# PSO36_BREKAOUT.net
KiCad netlist of a schematic drawn in EAGLE
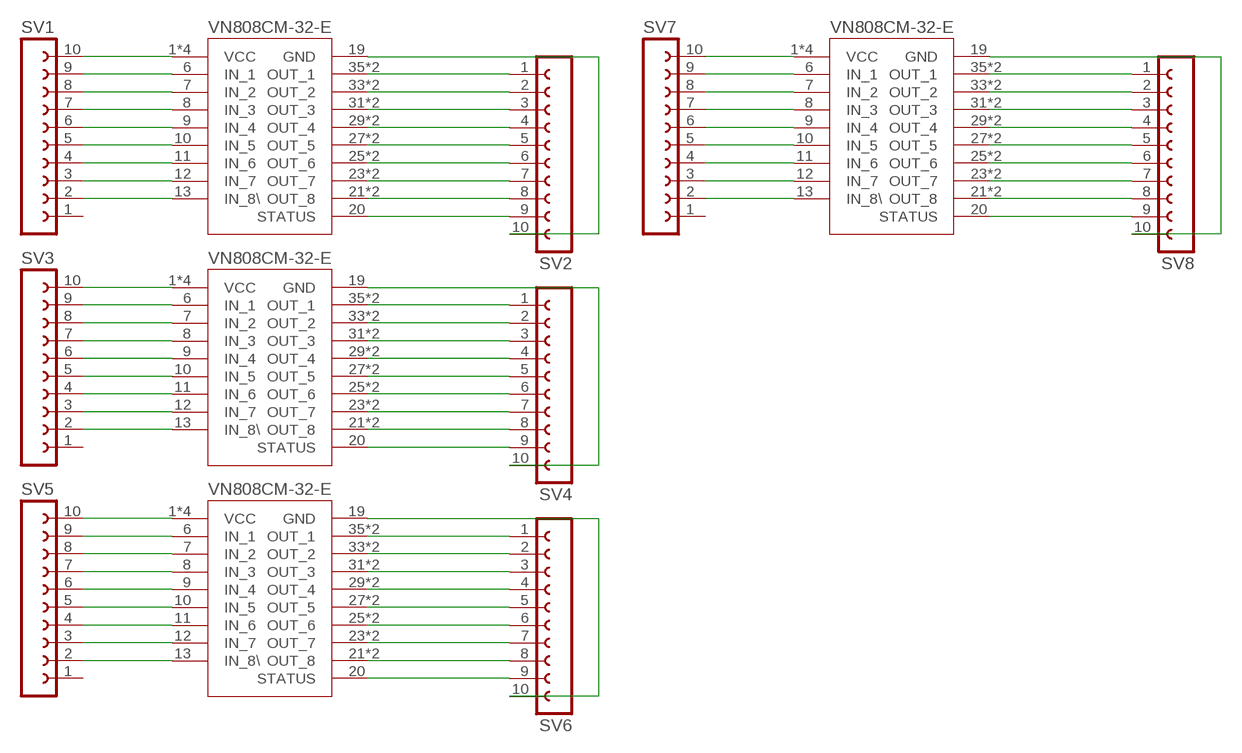
[diagram p0: schematic, sheet 1]

(export (version "E")
  (design (tool "Eeschema 10.0.6"))
  (components
    (comp (ref "SV1")
      (value "FE10-1")
      (footprint "eagle-import:FE10")
      (libsource (lib "eagle-import") (part "FE10-1"))
    )
    (comp (ref "SV2")
      (value "FE10-1")
      (footprint "eagle-import:FE10")
      (libsource (lib "eagle-import") (part "FE10-1"))
    )
    (comp (ref "SV3")
      (value "FE10-1")
      (footprint "eagle-import:FE10")
      (libsource (lib "eagle-import") (part "FE10-1"))
    )
    (comp (ref "SV4")
      (value "FE10-1")
      (footprint "eagle-import:FE10")
      (libsource (lib "eagle-import") (part "FE10-1"))
    )
    (comp (ref "SV5")
      (value "FE10-1")
      (footprint "eagle-import:FE10")
      (libsource (lib "eagle-import") (part "FE10-1"))
    )
    (comp (ref "SV6")
      (value "FE10-1")
      (footprint "eagle-import:FE10")
      (libsource (lib "eagle-import") (part "FE10-1"))
    )
    (comp (ref "SV7")
      (value "FE10-1")
      (footprint "eagle-import:FE10")
      (libsource (lib "eagle-import") (part "FE10-1"))
    )
    (comp (ref "SV8")
      (value "FE10-1")
      (footprint "eagle-import:FE10")
      (libsource (lib "eagle-import") (part "FE10-1"))
    )
    (comp (ref "U$1")
      (value "VN808CM-32-E")
      (footprint "eagle-import:PSO36")
      (libsource (lib "eagle-import") (part "VN808CM-32-E"))
    )
    (comp (ref "U$2")
      (value "VN808CM-32-E")
      (footprint "eagle-import:PSO36")
      (libsource (lib "eagle-import") (part "VN808CM-32-E"))
    )
    (comp (ref "U$3")
      (value "VN808CM-32-E")
      (footprint "eagle-import:PSO36")
      (libsource (lib "eagle-import") (part "VN808CM-32-E"))
    )
    (comp (ref "U$4")
      (value "VN808CM-32-E")
      (footprint "eagle-import:PSO36")
      (libsource (lib "eagle-import") (part "VN808CM-32-E"))
    )
  )
  (nets
    (net (code "1") (name "Net-(SV1-Pad10)") (class "Default")
      (node (ref "SV1") (pin "10") (pinfunction "10_10") (pintype "passive"))
      (node (ref "U$1") (pin "1") (pinfunction "VCC_1") (pintype "bidirectional"))
      (node (ref "U$1") (pin "M@1") (pinfunction "VCC_M@1") (pintype "bidirectional"))
      (node (ref "U$1") (pin "M@2") (pinfunction "VCC_M@2") (pintype "bidirectional"))
      (node (ref "U$1") (pin "M@3") (pinfunction "VCC_M@3") (pintype "bidirectional"))
    )
    (net (code "2") (name "Net-(SV2-Pad1)") (class "Default")
      (node (ref "SV2") (pin "1") (pinfunction "1_1") (pintype "passive"))
      (node (ref "U$1") (pin "35") (pinfunction "OUT_1_35") (pintype "bidirectional"))
      (node (ref "U$1") (pin "36") (pinfunction "OUT_1_36") (pintype "bidirectional"))
    )
    (net (code "3") (name "Net-(SV2-Pad2)") (class "Default")
      (node (ref "SV2") (pin "2") (pinfunction "2_2") (pintype "passive"))
      (node (ref "U$1") (pin "33") (pinfunction "OUT_2_33") (pintype "bidirectional"))
      (node (ref "U$1") (pin "34") (pinfunction "OUT_2_34") (pintype "bidirectional"))
    )
    (net (code "4") (name "Net-(SV2-Pad3)") (class "Default")
      (node (ref "SV2") (pin "3") (pinfunction "3_3") (pintype "passive"))
      (node (ref "U$1") (pin "31") (pinfunction "OUT_3_31") (pintype "bidirectional"))
      (node (ref "U$1") (pin "32") (pinfunction "OUT_3_32") (pintype "bidirectional"))
    )
    (net (code "5") (name "Net-(SV2-Pad4)") (class "Default")
      (node (ref "SV2") (pin "4") (pinfunction "4_4") (pintype "passive"))
      (node (ref "U$1") (pin "29") (pinfunction "OUT_4_29") (pintype "bidirectional"))
      (node (ref "U$1") (pin "30") (pinfunction "OUT_4_30") (pintype "bidirectional"))
    )
    (net (code "6") (name "Net-(SV2-Pad5)") (class "Default")
      (node (ref "SV2") (pin "5") (pinfunction "5_5") (pintype "passive"))
      (node (ref "U$1") (pin "27") (pinfunction "OUT_5_27") (pintype "bidirectional"))
      (node (ref "U$1") (pin "28") (pinfunction "OUT_5_28") (pintype "bidirectional"))
    )
    (net (code "7") (name "Net-(SV2-Pad6)") (class "Default")
      (node (ref "SV2") (pin "6") (pinfunction "6_6") (pintype "passive"))
      (node (ref "U$1") (pin "25") (pinfunction "OUT_6_25") (pintype "bidirectional"))
      (node (ref "U$1") (pin "26") (pinfunction "OUT_6_26") (pintype "bidirectional"))
    )
    (net (code "8") (name "Net-(SV2-Pad7)") (class "Default")
      (node (ref "SV2") (pin "7") (pinfunction "7_7") (pintype "passive"))
      (node (ref "U$1") (pin "23") (pinfunction "OUT_7_23") (pintype "bidirectional"))
      (node (ref "U$1") (pin "24") (pinfunction "OUT_7_24") (pintype "bidirectional"))
    )
    (net (code "9") (name "Net-(SV2-Pad8)") (class "Default")
      (node (ref "SV2") (pin "8") (pinfunction "8_8") (pintype "passive"))
      (node (ref "U$1") (pin "21") (pinfunction "OUT_8_21") (pintype "bidirectional"))
      (node (ref "U$1") (pin "22") (pinfunction "OUT_8_22") (pintype "bidirectional"))
    )
    (net (code "10") (name "Net-(SV3-Pad10)") (class "Default")
      (node (ref "SV3") (pin "10") (pinfunction "10_10") (pintype "passive"))
      (node (ref "U$2") (pin "1") (pinfunction "VCC_1") (pintype "bidirectional"))
      (node (ref "U$2") (pin "M@1") (pinfunction "VCC_M@1") (pintype "bidirectional"))
      (node (ref "U$2") (pin "M@2") (pinfunction "VCC_M@2") (pintype "bidirectional"))
      (node (ref "U$2") (pin "M@3") (pinfunction "VCC_M@3") (pintype "bidirectional"))
    )
    (net (code "11") (name "Net-(SV4-Pad1)") (class "Default")
      (node (ref "SV4") (pin "1") (pinfunction "1_1") (pintype "passive"))
      (node (ref "U$2") (pin "35") (pinfunction "OUT_1_35") (pintype "bidirectional"))
      (node (ref "U$2") (pin "36") (pinfunction "OUT_1_36") (pintype "bidirectional"))
    )
    (net (code "12") (name "Net-(SV4-Pad2)") (class "Default")
      (node (ref "SV4") (pin "2") (pinfunction "2_2") (pintype "passive"))
      (node (ref "U$2") (pin "33") (pinfunction "OUT_2_33") (pintype "bidirectional"))
      (node (ref "U$2") (pin "34") (pinfunction "OUT_2_34") (pintype "bidirectional"))
    )
    (net (code "13") (name "Net-(SV4-Pad3)") (class "Default")
      (node (ref "SV4") (pin "3") (pinfunction "3_3") (pintype "passive"))
      (node (ref "U$2") (pin "31") (pinfunction "OUT_3_31") (pintype "bidirectional"))
      (node (ref "U$2") (pin "32") (pinfunction "OUT_3_32") (pintype "bidirectional"))
    )
    (net (code "14") (name "Net-(SV4-Pad4)") (class "Default")
      (node (ref "SV4") (pin "4") (pinfunction "4_4") (pintype "passive"))
      (node (ref "U$2") (pin "29") (pinfunction "OUT_4_29") (pintype "bidirectional"))
      (node (ref "U$2") (pin "30") (pinfunction "OUT_4_30") (pintype "bidirectional"))
    )
    (net (code "15") (name "Net-(SV4-Pad5)") (class "Default")
      (node (ref "SV4") (pin "5") (pinfunction "5_5") (pintype "passive"))
      (node (ref "U$2") (pin "27") (pinfunction "OUT_5_27") (pintype "bidirectional"))
      (node (ref "U$2") (pin "28") (pinfunction "OUT_5_28") (pintype "bidirectional"))
    )
    (net (code "16") (name "Net-(SV4-Pad6)") (class "Default")
      (node (ref "SV4") (pin "6") (pinfunction "6_6") (pintype "passive"))
      (node (ref "U$2") (pin "25") (pinfunction "OUT_6_25") (pintype "bidirectional"))
      (node (ref "U$2") (pin "26") (pinfunction "OUT_6_26") (pintype "bidirectional"))
    )
    (net (code "17") (name "Net-(SV4-Pad7)") (class "Default")
      (node (ref "SV4") (pin "7") (pinfunction "7_7") (pintype "passive"))
      (node (ref "U$2") (pin "23") (pinfunction "OUT_7_23") (pintype "bidirectional"))
      (node (ref "U$2") (pin "24") (pinfunction "OUT_7_24") (pintype "bidirectional"))
    )
    (net (code "18") (name "Net-(SV4-Pad8)") (class "Default")
      (node (ref "SV4") (pin "8") (pinfunction "8_8") (pintype "passive"))
      (node (ref "U$2") (pin "21") (pinfunction "OUT_8_21") (pintype "bidirectional"))
      (node (ref "U$2") (pin "22") (pinfunction "OUT_8_22") (pintype "bidirectional"))
    )
    (net (code "19") (name "Net-(SV5-Pad10)") (class "Default")
      (node (ref "SV5") (pin "10") (pinfunction "10_10") (pintype "passive"))
      (node (ref "U$3") (pin "1") (pinfunction "VCC_1") (pintype "bidirectional"))
      (node (ref "U$3") (pin "M@1") (pinfunction "VCC_M@1") (pintype "bidirectional"))
      (node (ref "U$3") (pin "M@2") (pinfunction "VCC_M@2") (pintype "bidirectional"))
      (node (ref "U$3") (pin "M@3") (pinfunction "VCC_M@3") (pintype "bidirectional"))
    )
    (net (code "20") (name "Net-(SV6-Pad1)") (class "Default")
      (node (ref "SV6") (pin "1") (pinfunction "1_1") (pintype "passive"))
      (node (ref "U$3") (pin "35") (pinfunction "OUT_1_35") (pintype "bidirectional"))
      (node (ref "U$3") (pin "36") (pinfunction "OUT_1_36") (pintype "bidirectional"))
    )
    (net (code "21") (name "Net-(SV6-Pad2)") (class "Default")
      (node (ref "SV6") (pin "2") (pinfunction "2_2") (pintype "passive"))
      (node (ref "U$3") (pin "33") (pinfunction "OUT_2_33") (pintype "bidirectional"))
      (node (ref "U$3") (pin "34") (pinfunction "OUT_2_34") (pintype "bidirectional"))
    )
    (net (code "22") (name "Net-(SV6-Pad3)") (class "Default")
      (node (ref "SV6") (pin "3") (pinfunction "3_3") (pintype "passive"))
      (node (ref "U$3") (pin "31") (pinfunction "OUT_3_31") (pintype "bidirectional"))
      (node (ref "U$3") (pin "32") (pinfunction "OUT_3_32") (pintype "bidirectional"))
    )
    (net (code "23") (name "Net-(SV6-Pad4)") (class "Default")
      (node (ref "SV6") (pin "4") (pinfunction "4_4") (pintype "passive"))
      (node (ref "U$3") (pin "29") (pinfunction "OUT_4_29") (pintype "bidirectional"))
      (node (ref "U$3") (pin "30") (pinfunction "OUT_4_30") (pintype "bidirectional"))
    )
    (net (code "24") (name "Net-(SV6-Pad5)") (class "Default")
      (node (ref "SV6") (pin "5") (pinfunction "5_5") (pintype "passive"))
      (node (ref "U$3") (pin "27") (pinfunction "OUT_5_27") (pintype "bidirectional"))
      (node (ref "U$3") (pin "28") (pinfunction "OUT_5_28") (pintype "bidirectional"))
    )
    (net (code "25") (name "Net-(SV6-Pad6)") (class "Default")
      (node (ref "SV6") (pin "6") (pinfunction "6_6") (pintype "passive"))
      (node (ref "U$3") (pin "25") (pinfunction "OUT_6_25") (pintype "bidirectional"))
      (node (ref "U$3") (pin "26") (pinfunction "OUT_6_26") (pintype "bidirectional"))
    )
    (net (code "26") (name "Net-(SV6-Pad7)") (class "Default")
      (node (ref "SV6") (pin "7") (pinfunction "7_7") (pintype "passive"))
      (node (ref "U$3") (pin "23") (pinfunction "OUT_7_23") (pintype "bidirectional"))
      (node (ref "U$3") (pin "24") (pinfunction "OUT_7_24") (pintype "bidirectional"))
    )
    (net (code "27") (name "Net-(SV6-Pad8)") (class "Default")
      (node (ref "SV6") (pin "8") (pinfunction "8_8") (pintype "passive"))
      (node (ref "U$3") (pin "21") (pinfunction "OUT_8_21") (pintype "bidirectional"))
      (node (ref "U$3") (pin "22") (pinfunction "OUT_8_22") (pintype "bidirectional"))
    )
    (net (code "28") (name "Net-(SV7-Pad10)") (class "Default")
      (node (ref "SV7") (pin "10") (pinfunction "10_10") (pintype "passive"))
      (node (ref "U$4") (pin "1") (pinfunction "VCC_1") (pintype "bidirectional"))
      (node (ref "U$4") (pin "M@1") (pinfunction "VCC_M@1") (pintype "bidirectional"))
      (node (ref "U$4") (pin "M@2") (pinfunction "VCC_M@2") (pintype "bidirectional"))
      (node (ref "U$4") (pin "M@3") (pinfunction "VCC_M@3") (pintype "bidirectional"))
    )
    (net (code "29") (name "Net-(SV8-Pad1)") (class "Default")
      (node (ref "SV8") (pin "1") (pinfunction "1_1") (pintype "passive"))
      (node (ref "U$4") (pin "35") (pinfunction "OUT_1_35") (pintype "bidirectional"))
      (node (ref "U$4") (pin "36") (pinfunction "OUT_1_36") (pintype "bidirectional"))
    )
    (net (code "30") (name "Net-(SV8-Pad2)") (class "Default")
      (node (ref "SV8") (pin "2") (pinfunction "2_2") (pintype "passive"))
      (node (ref "U$4") (pin "33") (pinfunction "OUT_2_33") (pintype "bidirectional"))
      (node (ref "U$4") (pin "34") (pinfunction "OUT_2_34") (pintype "bidirectional"))
    )
    (net (code "31") (name "Net-(SV8-Pad3)") (class "Default")
      (node (ref "SV8") (pin "3") (pinfunction "3_3") (pintype "passive"))
      (node (ref "U$4") (pin "31") (pinfunction "OUT_3_31") (pintype "bidirectional"))
      (node (ref "U$4") (pin "32") (pinfunction "OUT_3_32") (pintype "bidirectional"))
    )
    (net (code "32") (name "Net-(SV8-Pad4)") (class "Default")
      (node (ref "SV8") (pin "4") (pinfunction "4_4") (pintype "passive"))
      (node (ref "U$4") (pin "29") (pinfunction "OUT_4_29") (pintype "bidirectional"))
      (node (ref "U$4") (pin "30") (pinfunction "OUT_4_30") (pintype "bidirectional"))
    )
    (net (code "33") (name "Net-(SV8-Pad5)") (class "Default")
      (node (ref "SV8") (pin "5") (pinfunction "5_5") (pintype "passive"))
      (node (ref "U$4") (pin "27") (pinfunction "OUT_5_27") (pintype "bidirectional"))
      (node (ref "U$4") (pin "28") (pinfunction "OUT_5_28") (pintype "bidirectional"))
    )
    (net (code "34") (name "Net-(SV8-Pad6)") (class "Default")
      (node (ref "SV8") (pin "6") (pinfunction "6_6") (pintype "passive"))
      (node (ref "U$4") (pin "25") (pinfunction "OUT_6_25") (pintype "bidirectional"))
      (node (ref "U$4") (pin "26") (pinfunction "OUT_6_26") (pintype "bidirectional"))
    )
    (net (code "35") (name "Net-(SV8-Pad7)") (class "Default")
      (node (ref "SV8") (pin "7") (pinfunction "7_7") (pintype "passive"))
      (node (ref "U$4") (pin "23") (pinfunction "OUT_7_23") (pintype "bidirectional"))
      (node (ref "U$4") (pin "24") (pinfunction "OUT_7_24") (pintype "bidirectional"))
    )
    (net (code "36") (name "Net-(SV8-Pad8)") (class "Default")
      (node (ref "SV8") (pin "8") (pinfunction "8_8") (pintype "passive"))
      (node (ref "U$4") (pin "21") (pinfunction "OUT_8_21") (pintype "bidirectional"))
      (node (ref "U$4") (pin "22") (pinfunction "OUT_8_22") (pintype "bidirectional"))
    )
    (net (code "37") (name "Net-(U$1-GND)") (class "Default")
      (node (ref "SV2") (pin "10") (pinfunction "10_10") (pintype "passive"))
      (node (ref "U$1") (pin "19") (pinfunction "GND_19") (pintype "bidirectional"))
    )
    (net (code "38") (name "Net-(U$1-IN_1)") (class "Default")
      (node (ref "SV1") (pin "9") (pinfunction "9_9") (pintype "passive"))
      (node (ref "U$1") (pin "6") (pinfunction "IN_1_6") (pintype "bidirectional"))
    )
    (net (code "39") (name "Net-(U$1-IN_2)") (class "Default")
      (node (ref "SV1") (pin "8") (pinfunction "8_8") (pintype "passive"))
      (node (ref "U$1") (pin "7") (pinfunction "IN_2_7") (pintype "bidirectional"))
    )
    (net (code "40") (name "Net-(U$1-IN_3)") (class "Default")
      (node (ref "SV1") (pin "7") (pinfunction "7_7") (pintype "passive"))
      (node (ref "U$1") (pin "8") (pinfunction "IN_3_8") (pintype "bidirectional"))
    )
    (net (code "41") (name "Net-(U$1-IN_4)") (class "Default")
      (node (ref "SV1") (pin "6") (pinfunction "6_6") (pintype "passive"))
      (node (ref "U$1") (pin "9") (pinfunction "IN_4_9") (pintype "bidirectional"))
    )
    (net (code "42") (name "Net-(U$1-IN_5)") (class "Default")
      (node (ref "SV1") (pin "5") (pinfunction "5_5") (pintype "passive"))
      (node (ref "U$1") (pin "10") (pinfunction "IN_5_10") (pintype "bidirectional"))
    )
    (net (code "43") (name "Net-(U$1-IN_6)") (class "Default")
      (node (ref "SV1") (pin "4") (pinfunction "4_4") (pintype "passive"))
      (node (ref "U$1") (pin "11") (pinfunction "IN_6_11") (pintype "bidirectional"))
    )
    (net (code "44") (name "Net-(U$1-IN_7)") (class "Default")
      (node (ref "SV1") (pin "3") (pinfunction "3_3") (pintype "passive"))
      (node (ref "U$1") (pin "12") (pinfunction "IN_7_12") (pintype "bidirectional"))
    )
    (net (code "45") (name "Net-(U$1-IN_8\\)") (class "Default")
      (node (ref "SV1") (pin "2") (pinfunction "2_2") (pintype "passive"))
      (node (ref "U$1") (pin "13") (pinfunction "IN_8\\_13") (pintype "bidirectional"))
    )
    (net (code "46") (name "Net-(U$1-STATUS)") (class "Default")
      (node (ref "SV2") (pin "9") (pinfunction "9_9") (pintype "passive"))
      (node (ref "U$1") (pin "20") (pinfunction "STATUS_20") (pintype "bidirectional"))
    )
    (net (code "47") (name "Net-(U$2-GND)") (class "Default")
      (node (ref "SV4") (pin "10") (pinfunction "10_10") (pintype "passive"))
      (node (ref "U$2") (pin "19") (pinfunction "GND_19") (pintype "bidirectional"))
    )
    (net (code "48") (name "Net-(U$2-IN_1)") (class "Default")
      (node (ref "SV3") (pin "9") (pinfunction "9_9") (pintype "passive"))
      (node (ref "U$2") (pin "6") (pinfunction "IN_1_6") (pintype "bidirectional"))
    )
    (net (code "49") (name "Net-(U$2-IN_2)") (class "Default")
      (node (ref "SV3") (pin "8") (pinfunction "8_8") (pintype "passive"))
      (node (ref "U$2") (pin "7") (pinfunction "IN_2_7") (pintype "bidirectional"))
    )
    (net (code "50") (name "Net-(U$2-IN_3)") (class "Default")
      (node (ref "SV3") (pin "7") (pinfunction "7_7") (pintype "passive"))
      (node (ref "U$2") (pin "8") (pinfunction "IN_3_8") (pintype "bidirectional"))
    )
    (net (code "51") (name "Net-(U$2-IN_4)") (class "Default")
      (node (ref "SV3") (pin "6") (pinfunction "6_6") (pintype "passive"))
      (node (ref "U$2") (pin "9") (pinfunction "IN_4_9") (pintype "bidirectional"))
    )
    (net (code "52") (name "Net-(U$2-IN_5)") (class "Default")
      (node (ref "SV3") (pin "5") (pinfunction "5_5") (pintype "passive"))
      (node (ref "U$2") (pin "10") (pinfunction "IN_5_10") (pintype "bidirectional"))
    )
    (net (code "53") (name "Net-(U$2-IN_6)") (class "Default")
      (node (ref "SV3") (pin "4") (pinfunction "4_4") (pintype "passive"))
      (node (ref "U$2") (pin "11") (pinfunction "IN_6_11") (pintype "bidirectional"))
    )
    (net (code "54") (name "Net-(U$2-IN_7)") (class "Default")
      (node (ref "SV3") (pin "3") (pinfunction "3_3") (pintype "passive"))
      (node (ref "U$2") (pin "12") (pinfunction "IN_7_12") (pintype "bidirectional"))
    )
    (net (code "55") (name "Net-(U$2-IN_8\\)") (class "Default")
      (node (ref "SV3") (pin "2") (pinfunction "2_2") (pintype "passive"))
      (node (ref "U$2") (pin "13") (pinfunction "IN_8\\_13") (pintype "bidirectional"))
    )
    (net (code "56") (name "Net-(U$2-STATUS)") (class "Default")
      (node (ref "SV4") (pin "9") (pinfunction "9_9") (pintype "passive"))
      (node (ref "U$2") (pin "20") (pinfunction "STATUS_20") (pintype "bidirectional"))
    )
    (net (code "57") (name "Net-(U$3-GND)") (class "Default")
      (node (ref "SV6") (pin "10") (pinfunction "10_10") (pintype "passive"))
      (node (ref "U$3") (pin "19") (pinfunction "GND_19") (pintype "bidirectional"))
    )
    (net (code "58") (name "Net-(U$3-IN_1)") (class "Default")
      (node (ref "SV5") (pin "9") (pinfunction "9_9") (pintype "passive"))
      (node (ref "U$3") (pin "6") (pinfunction "IN_1_6") (pintype "bidirectional"))
    )
    (net (code "59") (name "Net-(U$3-IN_2)") (class "Default")
      (node (ref "SV5") (pin "8") (pinfunction "8_8") (pintype "passive"))
      (node (ref "U$3") (pin "7") (pinfunction "IN_2_7") (pintype "bidirectional"))
    )
    (net (code "60") (name "Net-(U$3-IN_3)") (class "Default")
      (node (ref "SV5") (pin "7") (pinfunction "7_7") (pintype "passive"))
      (node (ref "U$3") (pin "8") (pinfunction "IN_3_8") (pintype "bidirectional"))
    )
    (net (code "61") (name "Net-(U$3-IN_4)") (class "Default")
      (node (ref "SV5") (pin "6") (pinfunction "6_6") (pintype "passive"))
      (node (ref "U$3") (pin "9") (pinfunction "IN_4_9") (pintype "bidirectional"))
    )
    (net (code "62") (name "Net-(U$3-IN_5)") (class "Default")
      (node (ref "SV5") (pin "5") (pinfunction "5_5") (pintype "passive"))
      (node (ref "U$3") (pin "10") (pinfunction "IN_5_10") (pintype "bidirectional"))
    )
    (net (code "63") (name "Net-(U$3-IN_6)") (class "Default")
      (node (ref "SV5") (pin "4") (pinfunction "4_4") (pintype "passive"))
      (node (ref "U$3") (pin "11") (pinfunction "IN_6_11") (pintype "bidirectional"))
    )
    (net (code "64") (name "Net-(U$3-IN_7)") (class "Default")
      (node (ref "SV5") (pin "3") (pinfunction "3_3") (pintype "passive"))
      (node (ref "U$3") (pin "12") (pinfunction "IN_7_12") (pintype "bidirectional"))
    )
    (net (code "65") (name "Net-(U$3-IN_8\\)") (class "Default")
      (node (ref "SV5") (pin "2") (pinfunction "2_2") (pintype "passive"))
      (node (ref "U$3") (pin "13") (pinfunction "IN_8\\_13") (pintype "bidirectional"))
    )
    (net (code "66") (name "Net-(U$3-STATUS)") (class "Default")
      (node (ref "SV6") (pin "9") (pinfunction "9_9") (pintype "passive"))
      (node (ref "U$3") (pin "20") (pinfunction "STATUS_20") (pintype "bidirectional"))
    )
    (net (code "67") (name "Net-(U$4-GND)") (class "Default")
      (node (ref "SV8") (pin "10") (pinfunction "10_10") (pintype "passive"))
      (node (ref "U$4") (pin "19") (pinfunction "GND_19") (pintype "bidirectional"))
    )
    (net (code "68") (name "Net-(U$4-IN_1)") (class "Default")
      (node (ref "SV7") (pin "9") (pinfunction "9_9") (pintype "passive"))
      (node (ref "U$4") (pin "6") (pinfunction "IN_1_6") (pintype "bidirectional"))
    )
    (net (code "69") (name "Net-(U$4-IN_2)") (class "Default")
      (node (ref "SV7") (pin "8") (pinfunction "8_8") (pintype "passive"))
      (node (ref "U$4") (pin "7") (pinfunction "IN_2_7") (pintype "bidirectional"))
    )
    (net (code "70") (name "Net-(U$4-IN_3)") (class "Default")
      (node (ref "SV7") (pin "7") (pinfunction "7_7") (pintype "passive"))
      (node (ref "U$4") (pin "8") (pinfunction "IN_3_8") (pintype "bidirectional"))
    )
    (net (code "71") (name "Net-(U$4-IN_4)") (class "Default")
      (node (ref "SV7") (pin "6") (pinfunction "6_6") (pintype "passive"))
      (node (ref "U$4") (pin "9") (pinfunction "IN_4_9") (pintype "bidirectional"))
    )
    (net (code "72") (name "Net-(U$4-IN_5)") (class "Default")
      (node (ref "SV7") (pin "5") (pinfunction "5_5") (pintype "passive"))
      (node (ref "U$4") (pin "10") (pinfunction "IN_5_10") (pintype "bidirectional"))
    )
    (net (code "73") (name "Net-(U$4-IN_6)") (class "Default")
      (node (ref "SV7") (pin "4") (pinfunction "4_4") (pintype "passive"))
      (node (ref "U$4") (pin "11") (pinfunction "IN_6_11") (pintype "bidirectional"))
    )
    (net (code "74") (name "Net-(U$4-IN_7)") (class "Default")
      (node (ref "SV7") (pin "3") (pinfunction "3_3") (pintype "passive"))
      (node (ref "U$4") (pin "12") (pinfunction "IN_7_12") (pintype "bidirectional"))
    )
    (net (code "75") (name "Net-(U$4-IN_8\\)") (class "Default")
      (node (ref "SV7") (pin "2") (pinfunction "2_2") (pintype "passive"))
      (node (ref "U$4") (pin "13") (pinfunction "IN_8\\_13") (pintype "bidirectional"))
    )
    (net (code "76") (name "Net-(U$4-STATUS)") (class "Default")
      (node (ref "SV8") (pin "9") (pinfunction "9_9") (pintype "passive"))
      (node (ref "U$4") (pin "20") (pinfunction "STATUS_20") (pintype "bidirectional"))
    )
    (net (code "77") (name "unconnected-(SV1-Pad1)") (class "Default")
      (node (ref "SV1") (pin "1") (pinfunction "1_1") (pintype "passive"))
    )
    (net (code "78") (name "unconnected-(SV3-Pad1)") (class "Default")
      (node (ref "SV3") (pin "1") (pinfunction "1_1") (pintype "passive"))
    )
    (net (code "79") (name "unconnected-(SV5-Pad1)") (class "Default")
      (node (ref "SV5") (pin "1") (pinfunction "1_1") (pintype "passive"))
    )
    (net (code "80") (name "unconnected-(SV7-Pad1)") (class "Default")
      (node (ref "SV7") (pin "1") (pinfunction "1_1") (pintype "passive"))
    )
  )
)
